# baseControl.net
KiCad netlist of a schematic drawn in Altium Designer
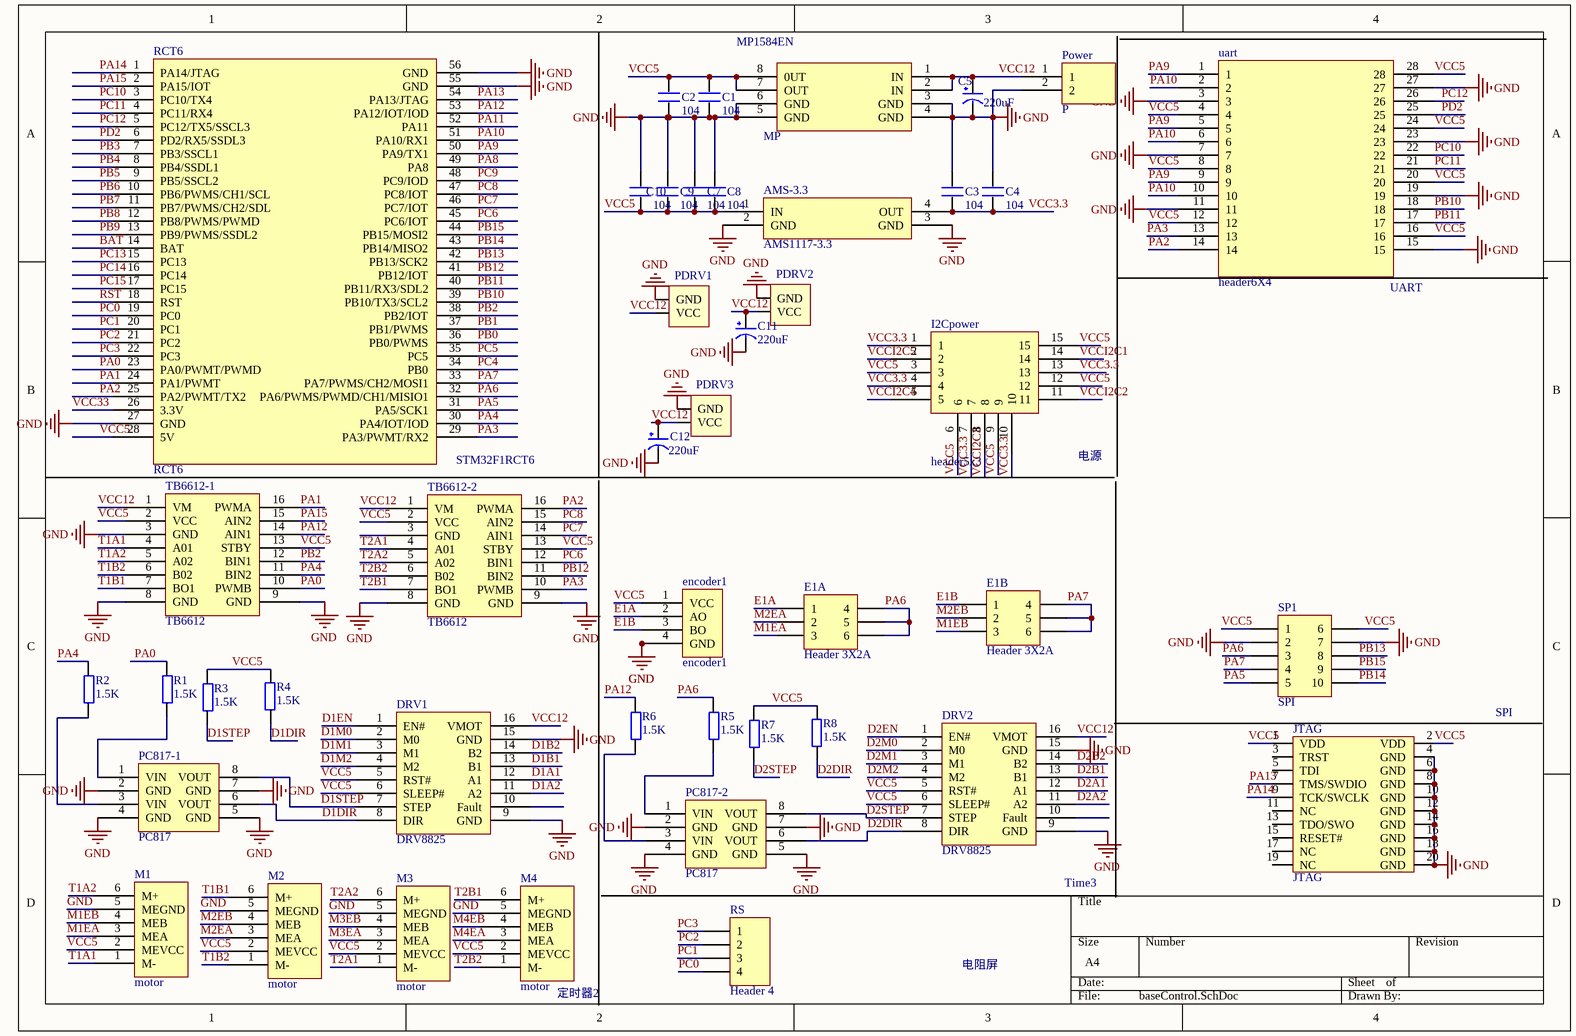
[diagram p0: baseControl.SchDoc]

(export (version "E")
  (design (tool "Eeschema 10.0.6"))
  (components
    (comp (ref "AMS-3.3")
      (value "AMS1117-3.3")
      (footprint "AMS1117-3.3")
      (libsource (lib "controlBsae") (part "AMS1117-3.3"))
    )
    (comp (ref "C1") (value "104") (footprint "0603P") (libsource (lib "CORE") (part "C")))
    (comp (ref "C2") (value "104") (footprint "0603P") (libsource (lib "CORE") (part "C")))
    (comp (ref "C3") (value "104") (footprint "0603P") (libsource (lib "CORE") (part "C")))
    (comp (ref "C4") (value "104") (footprint "0603P") (libsource (lib "CORE") (part "C")))
    (comp (ref "C5") (value "220uF") (footprint "220 25V") (libsource (lib "CORE") (part "CAP")))
    (comp (ref "C7") (value "104") (footprint "0805") (libsource (lib "CORE") (part "C")))
    (comp (ref "C8") (value "104") (footprint "0805") (libsource (lib "CORE") (part "C")))
    (comp (ref "C9") (value "104") (footprint "0805") (libsource (lib "CORE") (part "C")))
    (comp (ref "C10") (value "104") (footprint "0805") (libsource (lib "CORE") (part "C")))
    (comp (ref "C11") (value "220uF") (footprint "220 25V") (libsource (lib "CORE") (part "CAP")))
    (comp (ref "C12") (value "220uF") (footprint "220 25V") (libsource (lib "CORE") (part "CAP")))
    (comp (ref "DRV1")
      (value "DRV8825")
      (footprint "DRV8825")
      (libsource (lib "controlBsae") (part "DRV8825"))
    )
    (comp (ref "DRV2")
      (value "DRV8825")
      (footprint "DRV8825")
      (libsource (lib "controlBsae") (part "DRV8825"))
    )
    (comp (ref "E1A")
      (value "Header 3X2A")
      (footprint "HDR2X3_CEN")
      (description "Header, 3-Pin, Dual row")
      (fields (field (name "PUBLISHER") "Altium Limited"))
      (libsource (lib "Miscellaneous Connectors") (part "Header 3X2A"))
    )
    (comp (ref "E1B")
      (value "Header 3X2A")
      (footprint "HDR2X3_CEN")
      (description "Header, 3-Pin, Dual row")
      (fields (field (name "PUBLISHER") "Altium Limited"))
      (libsource (lib "Miscellaneous Connectors") (part "Header 3X2A"))
    )
    (comp (ref "encoder1")
      (value "encoder1")
      (footprint "XH-4-254")
      (libsource (lib "controlBsae") (part "encoder"))
    )
    (comp (ref "I2Cpower")
      (value "header5x3")
      (footprint "header5X3")
      (libsource (lib "baseControl") (part "header5x3"))
    )
    (comp (ref "JTAG") (value "JTAG") (footprint "JTAG_20") (libsource (lib "CORE") (part "JTAG_20")))
    (comp (ref "M1") (value "motor") (footprint "XH-6-254") (libsource (lib "controlBsae") (part "XH-6-254")))
    (comp (ref "M2") (value "motor") (footprint "XH-6-254") (libsource (lib "controlBsae") (part "XH-6-254")))
    (comp (ref "M3") (value "motor") (footprint "XH-6-254") (libsource (lib "controlBsae") (part "XH-6-254")))
    (comp (ref "M4") (value "motor") (footprint "XH-6-254") (libsource (lib "controlBsae") (part "XH-6-254")))
    (comp (ref "MP")
      (value "MP1584EN")
      (footprint "MP1584EN")
      (libsource (lib "controlBsae") (part "MP1584EN"))
    )
    (comp (ref "PC817-1") (value "PC817") (footprint "DIP4") (libsource (lib "controlBsae") (part "PC817")))
    (comp (ref "PC817-2") (value "PC817") (footprint "DIP4") (libsource (lib "controlBsae") (part "PC817")))
    (comp (ref "PDRV1")
      (value "XH2.54-2P")
      (footprint "XH2.54-2P")
      (libsource (lib "CORE") (part "XH2.54-2P"))
    )
    (comp (ref "PDRV2")
      (value "XH2.54-2P")
      (footprint "XH2.54-2P")
      (libsource (lib "CORE") (part "XH2.54-2P"))
    )
    (comp (ref "PDRV3")
      (value "XH2.54-2P")
      (footprint "XH2.54-2P")
      (libsource (lib "CORE") (part "XH2.54-2P"))
    )
    (comp (ref "Power") (value "P") (footprint "Power") (libsource (lib "controlBsae") (part "Power")))
    (comp (ref "R1") (value "1.5K") (footprint "0603P") (libsource (lib "CORE") (part "R")))
    (comp (ref "R2") (value "1.5K") (footprint "0603P") (libsource (lib "CORE") (part "R")))
    (comp (ref "R3") (value "1.5K") (footprint "0603P") (libsource (lib "CORE") (part "R")))
    (comp (ref "R4") (value "1.5K") (footprint "0603P") (libsource (lib "CORE") (part "R")))
    (comp (ref "R5") (value "1.5K") (footprint "0603P") (libsource (lib "CORE") (part "R")))
    (comp (ref "R6") (value "1.5K") (footprint "0603P") (libsource (lib "CORE") (part "R")))
    (comp (ref "R7") (value "1.5K") (footprint "0603P") (libsource (lib "CORE") (part "R")))
    (comp (ref "R8") (value "1.5K") (footprint "0603P") (libsource (lib "CORE") (part "R")))
    (comp (ref "RCT6")
      (value "RCT6")
      (footprint "STM32F1RCT6")
      (libsource (lib "controlBsae") (part "STM32F1RCT6"))
    )
    (comp (ref "RS")
      (value "Header 4")
      (footprint "HDR1X4")
      (description "Header, 4-Pin")
      (fields (field (name "PUBLISHER") "Altium Limited"))
      (libsource (lib "Miscellaneous Connectors") (part "Header 4"))
    )
    (comp (ref "SP1")
      (value "SPI")
      (footprint "HDR2X5_CEN")
      (description "Header, 5-Pin, Dual row")
      (fields (field (name "PUBLISHER") "Altium Limited"))
      (libsource (lib "Miscellaneous Connectors") (part "Header 5X2A"))
    )
    (comp (ref "TB6612-1")
      (value "TB6612")
      (footprint "TB6612")
      (libsource (lib "controlBsae") (part "TB6612"))
    )
    (comp (ref "TB6612-2")
      (value "TB6612")
      (footprint "TB6612")
      (libsource (lib "controlBsae") (part "TB6612"))
    )
    (comp (ref "uart")
      (value "header6X4")
      (footprint "header7X4")
      (libsource (lib "baseControl") (part "header6X4"))
    )
  )
  (nets
    (net (code "1") (name "/BAT") (class "Default")
      (node (ref "RCT6") (pin "14") (pinfunction "BAT_14") (pintype "passive"))
    )
    (net (code "2") (name "/D1A1") (class "Default")
      (node (ref "DRV1") (pin "12") (pinfunction "A1_12") (pintype "passive"))
    )
    (net (code "3") (name "/D1A2") (class "Default")
      (node (ref "DRV1") (pin "11") (pinfunction "A2_11") (pintype "passive"))
    )
    (net (code "4") (name "/D1B1") (class "Default")
      (node (ref "DRV1") (pin "13") (pinfunction "B1_13") (pintype "passive"))
    )
    (net (code "5") (name "/D1B2") (class "Default")
      (node (ref "DRV1") (pin "14") (pinfunction "B2_14") (pintype "passive"))
    )
    (net (code "6") (name "/D1DIR") (class "Default")
      (node (ref "DRV1") (pin "8") (pinfunction "DIR_8") (pintype "passive"))
      (node (ref "PC817-1") (pin "6") (pinfunction "VOUT_6") (pintype "passive"))
      (node (ref "R4") (pin "2") (pintype "passive"))
    )
    (net (code "7") (name "/D1EN") (class "Default")
      (node (ref "DRV1") (pin "1") (pinfunction "EN#_1") (pintype "passive"))
    )
    (net (code "8") (name "/D1M0") (class "Default")
      (node (ref "DRV1") (pin "2") (pinfunction "M0_2") (pintype "passive"))
    )
    (net (code "9") (name "/D1M1") (class "Default")
      (node (ref "DRV1") (pin "3") (pinfunction "M1_3") (pintype "passive"))
    )
    (net (code "10") (name "/D1M2") (class "Default")
      (node (ref "DRV1") (pin "4") (pinfunction "M2_4") (pintype "passive"))
    )
    (net (code "11") (name "/D1STEP") (class "Default")
      (node (ref "DRV1") (pin "7") (pinfunction "STEP_7") (pintype "passive"))
      (node (ref "PC817-1") (pin "8") (pinfunction "VOUT_8") (pintype "passive"))
      (node (ref "R3") (pin "1") (pintype "passive"))
    )
    (net (code "12") (name "/D2A1") (class "Default")
      (node (ref "DRV2") (pin "12") (pinfunction "A1_12") (pintype "passive"))
    )
    (net (code "13") (name "/D2A2") (class "Default")
      (node (ref "DRV2") (pin "11") (pinfunction "A2_11") (pintype "passive"))
    )
    (net (code "14") (name "/D2B1") (class "Default")
      (node (ref "DRV2") (pin "13") (pinfunction "B1_13") (pintype "passive"))
    )
    (net (code "15") (name "/D2B2") (class "Default")
      (node (ref "DRV2") (pin "14") (pinfunction "B2_14") (pintype "passive"))
    )
    (net (code "16") (name "/D2DIR") (class "Default")
      (node (ref "DRV2") (pin "8") (pinfunction "DIR_8") (pintype "passive"))
      (node (ref "PC817-2") (pin "6") (pinfunction "VOUT_6") (pintype "passive"))
      (node (ref "R8") (pin "2") (pintype "passive"))
    )
    (net (code "17") (name "/D2EN") (class "Default")
      (node (ref "DRV2") (pin "1") (pinfunction "EN#_1") (pintype "passive"))
    )
    (net (code "18") (name "/D2M0") (class "Default")
      (node (ref "DRV2") (pin "2") (pinfunction "M0_2") (pintype "passive"))
    )
    (net (code "19") (name "/D2M1") (class "Default")
      (node (ref "DRV2") (pin "3") (pinfunction "M1_3") (pintype "passive"))
    )
    (net (code "20") (name "/D2M2") (class "Default")
      (node (ref "DRV2") (pin "4") (pinfunction "M2_4") (pintype "passive"))
    )
    (net (code "21") (name "/D2STEP") (class "Default")
      (node (ref "DRV2") (pin "7") (pinfunction "STEP_7") (pintype "passive"))
      (node (ref "PC817-2") (pin "8") (pinfunction "VOUT_8") (pintype "passive"))
      (node (ref "R7") (pin "1") (pintype "passive"))
    )
    (net (code "22") (name "/E1A") (class "Default")
      (node (ref "E1A") (pin "1") (pinfunction "1_1") (pintype "passive"))
      (node (ref "encoder1") (pin "2") (pinfunction "AO_2") (pintype "passive"))
    )
    (net (code "23") (name "/E1B") (class "Default")
      (node (ref "E1B") (pin "1") (pinfunction "1_1") (pintype "passive"))
      (node (ref "encoder1") (pin "3") (pinfunction "BO_3") (pintype "passive"))
    )
    (net (code "24") (name "/M1EA") (class "Default")
      (node (ref "E1A") (pin "3") (pinfunction "3_3") (pintype "passive"))
      (node (ref "M1") (pin "3") (pinfunction "MEA_3") (pintype "passive"))
    )
    (net (code "25") (name "/M1EB") (class "Default")
      (node (ref "E1B") (pin "3") (pinfunction "3_3") (pintype "passive"))
      (node (ref "M1") (pin "4") (pinfunction "MEB_4") (pintype "passive"))
    )
    (net (code "26") (name "/M2EA") (class "Default")
      (node (ref "E1A") (pin "2") (pinfunction "2_2") (pintype "passive"))
      (node (ref "M2") (pin "3") (pinfunction "MEA_3") (pintype "passive"))
    )
    (net (code "27") (name "/M2EB") (class "Default")
      (node (ref "E1B") (pin "2") (pinfunction "2_2") (pintype "passive"))
      (node (ref "M2") (pin "4") (pinfunction "MEB_4") (pintype "passive"))
    )
    (net (code "28") (name "/M3EA") (class "Default")
      (node (ref "M3") (pin "3") (pinfunction "MEA_3") (pintype "passive"))
    )
    (net (code "29") (name "/M3EB") (class "Default")
      (node (ref "M3") (pin "4") (pinfunction "MEB_4") (pintype "passive"))
    )
    (net (code "30") (name "/M4EA") (class "Default")
      (node (ref "M4") (pin "3") (pinfunction "MEA_3") (pintype "passive"))
    )
    (net (code "31") (name "/M4EB") (class "Default")
      (node (ref "M4") (pin "4") (pinfunction "MEB_4") (pintype "passive"))
    )
    (net (code "32") (name "/PA0") (class "Default")
      (node (ref "R1") (pin "2") (pintype "passive"))
      (node (ref "RCT6") (pin "23") (pinfunction "PA0/PWMT/PWMD_23") (pintype "passive"))
      (node (ref "TB6612-1") (pin "10") (pinfunction "PWMB_10") (pintype "passive"))
    )
    (net (code "33") (name "/PA1") (class "Default")
      (node (ref "RCT6") (pin "24") (pinfunction "PA1/PWMT_24") (pintype "passive"))
      (node (ref "TB6612-1") (pin "16") (pinfunction "PWMA_16") (pintype "passive"))
    )
    (net (code "34") (name "/PA2") (class "Default")
      (node (ref "RCT6") (pin "25") (pinfunction "PA2/PWMT/TX2_25") (pintype "passive"))
      (node (ref "TB6612-2") (pin "16") (pinfunction "PWMA_16") (pintype "passive"))
      (node (ref "uart") (pin "14") (pinfunction "14_14") (pintype "passive"))
    )
    (net (code "35") (name "/PA3") (class "Default")
      (node (ref "RCT6") (pin "29") (pinfunction "PA3/PWMT/RX2_29") (pintype "passive"))
      (node (ref "TB6612-2") (pin "10") (pinfunction "PWMB_10") (pintype "passive"))
      (node (ref "uart") (pin "13") (pinfunction "13_13") (pintype "passive"))
    )
    (net (code "36") (name "/PA4") (class "Default")
      (node (ref "R2") (pin "2") (pintype "passive"))
      (node (ref "RCT6") (pin "30") (pinfunction "PA4/IOT/IOD_30") (pintype "passive"))
      (node (ref "TB6612-1") (pin "11") (pinfunction "BIN2_11") (pintype "passive"))
    )
    (net (code "37") (name "/PA5") (class "Default")
      (node (ref "RCT6") (pin "31") (pinfunction "PA5/SCK1_31") (pintype "passive"))
      (node (ref "SP1") (pin "5") (pinfunction "5_5") (pintype "passive"))
    )
    (net (code "38") (name "/PA6") (class "Default")
      (node (ref "E1A") (pin "4") (pinfunction "4_4") (pintype "passive"))
      (node (ref "E1A") (pin "5") (pinfunction "5_5") (pintype "passive"))
      (node (ref "E1A") (pin "6") (pinfunction "6_6") (pintype "passive"))
      (node (ref "R5") (pin "2") (pintype "passive"))
      (node (ref "RCT6") (pin "32") (pinfunction "PA6/PWMS/PWMD/CH1/MISIO1_32") (pintype "passive"))
      (node (ref "SP1") (pin "3") (pinfunction "3_3") (pintype "passive"))
    )
    (net (code "39") (name "/PA7") (class "Default")
      (node (ref "E1B") (pin "4") (pinfunction "4_4") (pintype "passive"))
      (node (ref "E1B") (pin "5") (pinfunction "5_5") (pintype "passive"))
      (node (ref "E1B") (pin "6") (pinfunction "6_6") (pintype "passive"))
      (node (ref "RCT6") (pin "33") (pinfunction "PA7/PWMS/CH2/MOSI1_33") (pintype "passive"))
      (node (ref "SP1") (pin "4") (pinfunction "4_4") (pintype "passive"))
    )
    (net (code "40") (name "/PA8") (class "Default")
      (node (ref "RCT6") (pin "49") (pinfunction "PA8_49") (pintype "passive"))
    )
    (net (code "41") (name "/PA9") (class "Default")
      (node (ref "RCT6") (pin "50") (pinfunction "PA9/TX1_50") (pintype "passive"))
      (node (ref "uart") (pin "1") (pinfunction "1_1") (pintype "passive"))
      (node (ref "uart") (pin "5") (pinfunction "5_5") (pintype "passive"))
      (node (ref "uart") (pin "9") (pinfunction "9_9") (pintype "passive"))
    )
    (net (code "42") (name "/PA10") (class "Default")
      (node (ref "RCT6") (pin "51") (pinfunction "PA10/RX1_51") (pintype "passive"))
      (node (ref "uart") (pin "10") (pinfunction "10_10") (pintype "passive"))
      (node (ref "uart") (pin "2") (pinfunction "2_2") (pintype "passive"))
      (node (ref "uart") (pin "6") (pinfunction "6_6") (pintype "passive"))
    )
    (net (code "43") (name "/PA11") (class "Default")
      (node (ref "RCT6") (pin "52") (pinfunction "PA11_52") (pintype "passive"))
    )
    (net (code "44") (name "/PA12") (class "Default")
      (node (ref "R6") (pin "2") (pintype "passive"))
      (node (ref "RCT6") (pin "53") (pinfunction "PA12/IOT/IOD_53") (pintype "passive"))
      (node (ref "TB6612-1") (pin "14") (pinfunction "AIN1_14") (pintype "passive"))
    )
    (net (code "45") (name "/PA13") (class "Default")
      (node (ref "JTAG") (pin "7") (pinfunction "TMS/SWDIO_7") (pintype "passive"))
      (node (ref "RCT6") (pin "54") (pinfunction "PA13/JTAG_54") (pintype "passive"))
    )
    (net (code "46") (name "/PA14") (class "Default")
      (node (ref "JTAG") (pin "9") (pinfunction "TCK/SWCLK_9") (pintype "passive"))
      (node (ref "RCT6") (pin "1") (pinfunction "PA14/JTAG_1") (pintype "passive"))
    )
    (net (code "47") (name "/PA15") (class "Default")
      (node (ref "RCT6") (pin "2") (pinfunction "PA15/IOT_2") (pintype "passive"))
      (node (ref "TB6612-1") (pin "15") (pinfunction "AIN2_15") (pintype "passive"))
    )
    (net (code "48") (name "/PB0") (class "Default")
      (node (ref "RCT6") (pin "36") (pinfunction "PB0/PWMS_36") (pintype "passive"))
    )
    (net (code "49") (name "/PB1") (class "Default")
      (node (ref "RCT6") (pin "37") (pinfunction "PB1/PWMS_37") (pintype "passive"))
    )
    (net (code "50") (name "/PB2") (class "Default")
      (node (ref "RCT6") (pin "38") (pinfunction "PB2/IOT_38") (pintype "passive"))
      (node (ref "TB6612-1") (pin "12") (pinfunction "BIN1_12") (pintype "passive"))
    )
    (net (code "51") (name "/PB3") (class "Default")
      (node (ref "RCT6") (pin "7") (pinfunction "PB3/SSCL1_7") (pintype "passive"))
    )
    (net (code "52") (name "/PB4") (class "Default")
      (node (ref "RCT6") (pin "8") (pinfunction "PB4/SSDL1_8") (pintype "passive"))
    )
    (net (code "53") (name "/PB5") (class "Default")
      (node (ref "RCT6") (pin "9") (pinfunction "PB5/SSCL2_9") (pintype "passive"))
    )
    (net (code "54") (name "/PB6") (class "Default")
      (node (ref "RCT6") (pin "10") (pinfunction "PB6/PWMS/CH1/SCL_10") (pintype "passive"))
    )
    (net (code "55") (name "/PB7") (class "Default")
      (node (ref "RCT6") (pin "11") (pinfunction "PB7/PWMS/CH2/SDL_11") (pintype "passive"))
    )
    (net (code "56") (name "/PB8") (class "Default")
      (node (ref "RCT6") (pin "12") (pinfunction "PB8/PWMS/PWMD_12") (pintype "passive"))
    )
    (net (code "57") (name "/PB9") (class "Default")
      (node (ref "RCT6") (pin "13") (pinfunction "PB9/PWMS/SSDL2_13") (pintype "passive"))
    )
    (net (code "58") (name "/PB10") (class "Default")
      (node (ref "RCT6") (pin "39") (pinfunction "PB10/TX3/SCL2_39") (pintype "passive"))
      (node (ref "uart") (pin "18") (pinfunction "18_18") (pintype "passive"))
    )
    (net (code "59") (name "/PB11") (class "Default")
      (node (ref "RCT6") (pin "40") (pinfunction "PB11/RX3/SDL2_40") (pintype "passive"))
      (node (ref "uart") (pin "17") (pinfunction "17_17") (pintype "passive"))
    )
    (net (code "60") (name "/PB12") (class "Default")
      (node (ref "RCT6") (pin "41") (pinfunction "PB12/IOT_41") (pintype "passive"))
      (node (ref "TB6612-2") (pin "11") (pinfunction "BIN2_11") (pintype "passive"))
    )
    (net (code "61") (name "/PB13") (class "Default")
      (node (ref "RCT6") (pin "42") (pinfunction "PB13/SCK2_42") (pintype "passive"))
      (node (ref "SP1") (pin "8") (pinfunction "8_8") (pintype "passive"))
    )
    (net (code "62") (name "/PB14") (class "Default")
      (node (ref "RCT6") (pin "43") (pinfunction "PB14/MISO2_43") (pintype "passive"))
      (node (ref "SP1") (pin "10") (pinfunction "10_10") (pintype "passive"))
    )
    (net (code "63") (name "/PB15") (class "Default")
      (node (ref "RCT6") (pin "44") (pinfunction "PB15/MOSI2_44") (pintype "passive"))
      (node (ref "SP1") (pin "9") (pinfunction "9_9") (pintype "passive"))
    )
    (net (code "64") (name "/PC0") (class "Default")
      (node (ref "RCT6") (pin "19") (pinfunction "PC0_19") (pintype "passive"))
      (node (ref "RS") (pin "4") (pinfunction "4_4") (pintype "passive"))
    )
    (net (code "65") (name "/PC1") (class "Default")
      (node (ref "RCT6") (pin "20") (pinfunction "PC1_20") (pintype "passive"))
      (node (ref "RS") (pin "3") (pinfunction "3_3") (pintype "passive"))
    )
    (net (code "66") (name "/PC2") (class "Default")
      (node (ref "RCT6") (pin "21") (pinfunction "PC2_21") (pintype "passive"))
      (node (ref "RS") (pin "2") (pinfunction "2_2") (pintype "passive"))
    )
    (net (code "67") (name "/PC3") (class "Default")
      (node (ref "RCT6") (pin "22") (pinfunction "PC3_22") (pintype "passive"))
      (node (ref "RS") (pin "1") (pinfunction "1_1") (pintype "passive"))
    )
    (net (code "68") (name "/PC4") (class "Default")
      (node (ref "RCT6") (pin "34") (pinfunction "PB0_34") (pintype "passive"))
    )
    (net (code "69") (name "/PC5") (class "Default")
      (node (ref "RCT6") (pin "35") (pinfunction "PC5_35") (pintype "passive"))
    )
    (net (code "70") (name "/PC6") (class "Default")
      (node (ref "RCT6") (pin "45") (pinfunction "PC6/IOT_45") (pintype "passive"))
      (node (ref "TB6612-2") (pin "12") (pinfunction "BIN1_12") (pintype "passive"))
    )
    (net (code "71") (name "/PC7") (class "Default")
      (node (ref "RCT6") (pin "46") (pinfunction "PC7/IOT_46") (pintype "passive"))
      (node (ref "TB6612-2") (pin "14") (pinfunction "AIN1_14") (pintype "passive"))
    )
    (net (code "72") (name "/PC8") (class "Default")
      (node (ref "RCT6") (pin "47") (pinfunction "PC8/IOT_47") (pintype "passive"))
      (node (ref "TB6612-2") (pin "15") (pinfunction "AIN2_15") (pintype "passive"))
    )
    (net (code "73") (name "/PC9") (class "Default")
      (node (ref "RCT6") (pin "48") (pinfunction "PC9/IOD_48") (pintype "passive"))
    )
    (net (code "74") (name "/PC10") (class "Default")
      (node (ref "RCT6") (pin "3") (pinfunction "PC10/TX4_3") (pintype "passive"))
      (node (ref "uart") (pin "22") (pinfunction "22_22") (pintype "passive"))
    )
    (net (code "75") (name "/PC11") (class "Default")
      (node (ref "RCT6") (pin "4") (pinfunction "PC11/RX4_4") (pintype "passive"))
      (node (ref "uart") (pin "21") (pinfunction "21_21") (pintype "passive"))
    )
    (net (code "76") (name "/PC12") (class "Default")
      (node (ref "RCT6") (pin "5") (pinfunction "PC12/TX5/SSCL3_5") (pintype "passive"))
      (node (ref "uart") (pin "26") (pinfunction "26_26") (pintype "passive"))
    )
    (net (code "77") (name "/PC13") (class "Default")
      (node (ref "RCT6") (pin "15") (pinfunction "PC13_15") (pintype "passive"))
    )
    (net (code "78") (name "/PC14") (class "Default")
      (node (ref "RCT6") (pin "16") (pinfunction "PC14_16") (pintype "passive"))
    )
    (net (code "79") (name "/PC15") (class "Default")
      (node (ref "RCT6") (pin "17") (pinfunction "PC15_17") (pintype "passive"))
    )
    (net (code "80") (name "/PD2") (class "Default")
      (node (ref "RCT6") (pin "6") (pinfunction "PD2/RX5/SSDL3_6") (pintype "passive"))
      (node (ref "uart") (pin "25") (pinfunction "25_25") (pintype "passive"))
    )
    (net (code "81") (name "/RST") (class "Default")
      (node (ref "RCT6") (pin "18") (pinfunction "RST_18") (pintype "passive"))
    )
    (net (code "82") (name "/T1A1") (class "Default")
      (node (ref "M1") (pin "1") (pinfunction "M-_1") (pintype "passive"))
      (node (ref "TB6612-1") (pin "4") (pinfunction "A01_4") (pintype "passive"))
    )
    (net (code "83") (name "/T1A2") (class "Default")
      (node (ref "M1") (pin "6") (pinfunction "M+_6") (pintype "passive"))
      (node (ref "TB6612-1") (pin "5") (pinfunction "A02_5") (pintype "passive"))
    )
    (net (code "84") (name "/T1B1") (class "Default")
      (node (ref "M2") (pin "6") (pinfunction "M+_6") (pintype "passive"))
      (node (ref "TB6612-1") (pin "7") (pinfunction "BO1_7") (pintype "passive"))
    )
    (net (code "85") (name "/T1B2") (class "Default")
      (node (ref "M2") (pin "1") (pinfunction "M-_1") (pintype "passive"))
      (node (ref "TB6612-1") (pin "6") (pinfunction "B02_6") (pintype "passive"))
    )
    (net (code "86") (name "/T2A1") (class "Default")
      (node (ref "M3") (pin "1") (pinfunction "M-_1") (pintype "passive"))
      (node (ref "TB6612-2") (pin "4") (pinfunction "A01_4") (pintype "passive"))
    )
    (net (code "87") (name "/T2A2") (class "Default")
      (node (ref "M3") (pin "6") (pinfunction "M+_6") (pintype "passive"))
      (node (ref "TB6612-2") (pin "5") (pinfunction "A02_5") (pintype "passive"))
    )
    (net (code "88") (name "/T2B1") (class "Default")
      (node (ref "M4") (pin "6") (pinfunction "M+_6") (pintype "passive"))
      (node (ref "TB6612-2") (pin "7") (pinfunction "BO1_7") (pintype "passive"))
    )
    (net (code "89") (name "/T2B2") (class "Default")
      (node (ref "M4") (pin "1") (pinfunction "M-_1") (pintype "passive"))
      (node (ref "TB6612-2") (pin "6") (pinfunction "B02_6") (pintype "passive"))
    )
    (net (code "90") (name "/VCC3.3") (class "Default")
      (node (ref "AMS-3.3") (pin "4") (pinfunction "OUT_4") (pintype "passive"))
      (node (ref "C3") (pin "1") (pintype "passive"))
      (node (ref "C4") (pin "1") (pintype "passive"))
      (node (ref "I2Cpower") (pin "1") (pinfunction "1_1") (pintype "passive"))
      (node (ref "I2Cpower") (pin "10") (pinfunction "10_10") (pintype "passive"))
      (node (ref "I2Cpower") (pin "13") (pinfunction "13_13") (pintype "passive"))
      (node (ref "I2Cpower") (pin "4") (pinfunction "4_4") (pintype "passive"))
      (node (ref "I2Cpower") (pin "7") (pinfunction "7_7") (pintype "passive"))
    )
    (net (code "91") (name "/VCC5") (class "Default")
      (node (ref "AMS-3.3") (pin "1") (pinfunction "IN_1") (pintype "passive"))
      (node (ref "C1") (pin "1") (pintype "passive"))
      (node (ref "C10") (pin "1") (pintype "passive"))
      (node (ref "C2") (pin "1") (pintype "passive"))
      (node (ref "C7") (pin "1") (pintype "passive"))
      (node (ref "C8") (pin "1") (pintype "passive"))
      (node (ref "C9") (pin "1") (pintype "passive"))
      (node (ref "DRV1") (pin "5") (pinfunction "RST#_5") (pintype "passive"))
      (node (ref "DRV1") (pin "6") (pinfunction "SLEEP#_6") (pintype "passive"))
      (node (ref "DRV2") (pin "5") (pinfunction "RST#_5") (pintype "passive"))
      (node (ref "DRV2") (pin "6") (pinfunction "SLEEP#_6") (pintype "passive"))
      (node (ref "I2Cpower") (pin "12") (pinfunction "12_12") (pintype "passive"))
      (node (ref "I2Cpower") (pin "15") (pinfunction "15_15") (pintype "passive"))
      (node (ref "I2Cpower") (pin "3") (pinfunction "3_3") (pintype "passive"))
      (node (ref "I2Cpower") (pin "6") (pinfunction "6_6") (pintype "passive"))
      (node (ref "I2Cpower") (pin "9") (pinfunction "9_9") (pintype "passive"))
      (node (ref "JTAG") (pin "1") (pinfunction "VDD_1") (pintype "passive"))
      (node (ref "JTAG") (pin "2") (pinfunction "VDD_2") (pintype "passive"))
      (node (ref "M1") (pin "2") (pinfunction "MEVCC_2") (pintype "passive"))
      (node (ref "M2") (pin "2") (pinfunction "MEVCC_2") (pintype "passive"))
      (node (ref "M3") (pin "2") (pinfunction "MEVCC_2") (pintype "passive"))
      (node (ref "M4") (pin "2") (pinfunction "MEVCC_2") (pintype "passive"))
      (node (ref "MP") (pin "7") (pinfunction "OUT_7") (pintype "passive"))
      (node (ref "MP") (pin "8") (pinfunction "0UT_8") (pintype "passive"))
      (node (ref "R3") (pin "2") (pintype "passive"))
      (node (ref "R4") (pin "1") (pintype "passive"))
      (node (ref "R7") (pin "2") (pintype "passive"))
      (node (ref "R8") (pin "1") (pintype "passive"))
      (node (ref "RCT6") (pin "28") (pinfunction "5V_28") (pintype "passive"))
      (node (ref "SP1") (pin "1") (pinfunction "1_1") (pintype "passive"))
      (node (ref "SP1") (pin "6") (pinfunction "6_6") (pintype "passive"))
      (node (ref "TB6612-1") (pin "13") (pinfunction "STBY_13") (pintype "passive"))
      (node (ref "TB6612-1") (pin "2") (pinfunction "VCC_2") (pintype "passive"))
      (node (ref "TB6612-2") (pin "13") (pinfunction "STBY_13") (pintype "passive"))
      (node (ref "TB6612-2") (pin "2") (pinfunction "VCC_2") (pintype "passive"))
      (node (ref "encoder1") (pin "1") (pinfunction "VCC_1") (pintype "passive"))
      (node (ref "uart") (pin "12") (pinfunction "12_12") (pintype "passive"))
      (node (ref "uart") (pin "16") (pinfunction "16_16") (pintype "passive"))
      (node (ref "uart") (pin "20") (pinfunction "20_20") (pintype "passive"))
      (node (ref "uart") (pin "24") (pinfunction "24_24") (pintype "passive"))
      (node (ref "uart") (pin "28") (pinfunction "28_28") (pintype "passive"))
      (node (ref "uart") (pin "4") (pinfunction "4_4") (pintype "passive"))
      (node (ref "uart") (pin "8") (pinfunction "8_8") (pintype "passive"))
    )
    (net (code "92") (name "/VCC12") (class "Default")
      (node (ref "C11") (pin "1") (pinfunction "VCC_1") (pintype "passive"))
      (node (ref "C12") (pin "1") (pinfunction "VCC_1") (pintype "passive"))
      (node (ref "C5") (pin "1") (pinfunction "VCC_1") (pintype "passive"))
      (node (ref "DRV1") (pin "16") (pinfunction "VMOT_16") (pintype "passive"))
      (node (ref "DRV2") (pin "16") (pinfunction "VMOT_16") (pintype "passive"))
      (node (ref "MP") (pin "1") (pinfunction "IN_1") (pintype "passive"))
      (node (ref "MP") (pin "2") (pinfunction "IN_2") (pintype "passive"))
      (node (ref "PDRV1") (pin "2") (pinfunction "VCC_2") (pintype "passive"))
      (node (ref "PDRV2") (pin "2") (pinfunction "VCC_2") (pintype "passive"))
      (node (ref "PDRV3") (pin "2") (pinfunction "VCC_2") (pintype "passive"))
      (node (ref "Power") (pin "1") (pinfunction "1_1") (pintype "passive"))
      (node (ref "TB6612-1") (pin "1") (pinfunction "VM_1") (pintype "passive"))
      (node (ref "TB6612-2") (pin "1") (pinfunction "VM_1") (pintype "passive"))
    )
    (net (code "93") (name "/VCC33") (class "Default")
      (node (ref "RCT6") (pin "26") (pinfunction "3.3V_26") (pintype "passive"))
    )
    (net (code "94") (name "/VCCI2C1") (class "Default")
      (node (ref "I2Cpower") (pin "14") (pinfunction "14_14") (pintype "passive"))
    )
    (net (code "95") (name "/VCCI2C2") (class "Default")
      (node (ref "I2Cpower") (pin "11") (pinfunction "11_11") (pintype "passive"))
    )
    (net (code "96") (name "/VCCI2C3") (class "Default")
      (node (ref "I2Cpower") (pin "8") (pinfunction "8_8") (pintype "passive"))
    )
    (net (code "97") (name "/VCCI2C4") (class "Default")
      (node (ref "I2Cpower") (pin "5") (pinfunction "5_5") (pintype "passive"))
    )
    (net (code "98") (name "/VCCI2C5") (class "Default")
      (node (ref "I2Cpower") (pin "2") (pinfunction "2_2") (pintype "passive"))
    )
    (net (code "99") (name "GND") (class "Default")
      (node (ref "AMS-3.3") (pin "2") (pinfunction "GND_2") (pintype "passive"))
      (node (ref "AMS-3.3") (pin "3") (pinfunction "GND_3") (pintype "passive"))
      (node (ref "C1") (pin "2") (pintype "passive"))
      (node (ref "C10") (pin "2") (pintype "passive"))
      (node (ref "C11") (pin "2") (pinfunction "GND_2") (pintype "passive"))
      (node (ref "C12") (pin "2") (pinfunction "GND_2") (pintype "passive"))
      (node (ref "C2") (pin "2") (pintype "passive"))
      (node (ref "C3") (pin "2") (pintype "passive"))
      (node (ref "C4") (pin "2") (pintype "passive"))
      (node (ref "C5") (pin "2") (pinfunction "GND_2") (pintype "passive"))
      (node (ref "C7") (pin "2") (pintype "passive"))
      (node (ref "C8") (pin "2") (pintype "passive"))
      (node (ref "C9") (pin "2") (pintype "passive"))
      (node (ref "DRV1") (pin "15") (pinfunction "GND_15") (pintype "passive"))
      (node (ref "DRV1") (pin "9") (pinfunction "GND_9") (pintype "passive"))
      (node (ref "DRV2") (pin "15") (pinfunction "GND_15") (pintype "passive"))
      (node (ref "DRV2") (pin "9") (pinfunction "GND_9") (pintype "passive"))
      (node (ref "JTAG") (pin "10") (pinfunction "GND_10") (pintype "passive"))
      (node (ref "JTAG") (pin "12") (pinfunction "GND_12") (pintype "passive"))
      (node (ref "JTAG") (pin "14") (pinfunction "GND_14") (pintype "passive"))
      (node (ref "JTAG") (pin "16") (pinfunction "GND_16") (pintype "passive"))
      (node (ref "JTAG") (pin "18") (pinfunction "GND_18") (pintype "passive"))
      (node (ref "JTAG") (pin "20") (pinfunction "GND_20") (pintype "passive"))
      (node (ref "JTAG") (pin "4") (pinfunction "GND_4") (pintype "passive"))
      (node (ref "JTAG") (pin "6") (pinfunction "GND_6") (pintype "passive"))
      (node (ref "JTAG") (pin "8") (pinfunction "GND_8") (pintype "passive"))
      (node (ref "M1") (pin "5") (pinfunction "MEGND_5") (pintype "passive"))
      (node (ref "M2") (pin "5") (pinfunction "MEGND_5") (pintype "passive"))
      (node (ref "M3") (pin "5") (pinfunction "MEGND_5") (pintype "passive"))
      (node (ref "M4") (pin "5") (pinfunction "MEGND_5") (pintype "passive"))
      (node (ref "MP") (pin "3") (pinfunction "GND_3") (pintype "passive"))
      (node (ref "MP") (pin "4") (pinfunction "GND_4") (pintype "passive"))
      (node (ref "MP") (pin "5") (pinfunction "GND_5") (pintype "passive"))
      (node (ref "MP") (pin "6") (pinfunction "GND_6") (pintype "passive"))
      (node (ref "PC817-1") (pin "2") (pinfunction "GND_2") (pintype "passive"))
      (node (ref "PC817-1") (pin "4") (pinfunction "GND_4") (pintype "passive"))
      (node (ref "PC817-1") (pin "5") (pinfunction "GND_5") (pintype "passive"))
      (node (ref "PC817-1") (pin "7") (pinfunction "GND_7") (pintype "passive"))
      (node (ref "PC817-2") (pin "2") (pinfunction "GND_2") (pintype "passive"))
      (node (ref "PC817-2") (pin "4") (pinfunction "GND_4") (pintype "passive"))
      (node (ref "PC817-2") (pin "5") (pinfunction "GND_5") (pintype "passive"))
      (node (ref "PC817-2") (pin "7") (pinfunction "GND_7") (pintype "passive"))
      (node (ref "PDRV1") (pin "1") (pinfunction "GND_1") (pintype "passive"))
      (node (ref "PDRV2") (pin "1") (pinfunction "GND_1") (pintype "passive"))
      (node (ref "PDRV3") (pin "1") (pinfunction "GND_1") (pintype "passive"))
      (node (ref "Power") (pin "2") (pinfunction "2_2") (pintype "passive"))
      (node (ref "RCT6") (pin "27") (pinfunction "GND_27") (pintype "passive"))
      (node (ref "RCT6") (pin "55") (pinfunction "GND_55") (pintype "passive"))
      (node (ref "RCT6") (pin "56") (pinfunction "GND_56") (pintype "passive"))
      (node (ref "SP1") (pin "2") (pinfunction "2_2") (pintype "passive"))
      (node (ref "SP1") (pin "7") (pinfunction "7_7") (pintype "passive"))
      (node (ref "TB6612-1") (pin "3") (pinfunction "GND_3") (pintype "passive"))
      (node (ref "TB6612-1") (pin "8") (pinfunction "GND_8") (pintype "passive"))
      (node (ref "TB6612-1") (pin "9") (pinfunction "GND_9") (pintype "passive"))
      (node (ref "TB6612-2") (pin "8") (pinfunction "GND_8") (pintype "passive"))
      (node (ref "TB6612-2") (pin "9") (pinfunction "GND_9") (pintype "passive"))
      (node (ref "encoder1") (pin "4") (pinfunction "GND_4") (pintype "passive"))
      (node (ref "uart") (pin "11") (pinfunction "11_11") (pintype "passive"))
      (node (ref "uart") (pin "15") (pinfunction "15_15") (pintype "passive"))
      (node (ref "uart") (pin "19") (pinfunction "19_19") (pintype "passive"))
      (node (ref "uart") (pin "23") (pinfunction "23_23") (pintype "passive"))
      (node (ref "uart") (pin "27") (pinfunction "27_27") (pintype "passive"))
      (node (ref "uart") (pin "3") (pinfunction "3_3") (pintype "passive"))
      (node (ref "uart") (pin "7") (pinfunction "7_7") (pintype "passive"))
    )
    (net (code "100") (name "Net-(PC817-1-VIN-Pad1)") (class "Default")
      (node (ref "PC817-1") (pin "1") (pinfunction "VIN_1") (pintype "passive"))
      (node (ref "R1") (pin "1") (pintype "passive"))
    )
    (net (code "101") (name "Net-(PC817-1-VIN-Pad3)") (class "Default")
      (node (ref "PC817-1") (pin "3") (pinfunction "VIN_3") (pintype "passive"))
      (node (ref "R2") (pin "1") (pintype "passive"))
    )
    (net (code "102") (name "Net-(PC817-2-VIN-Pad1)") (class "Default")
      (node (ref "PC817-2") (pin "1") (pinfunction "VIN_1") (pintype "passive"))
      (node (ref "R5") (pin "1") (pintype "passive"))
    )
    (net (code "103") (name "Net-(PC817-2-VIN-Pad3)") (class "Default")
      (node (ref "PC817-2") (pin "3") (pinfunction "VIN_3") (pintype "passive"))
      (node (ref "R6") (pin "1") (pintype "passive"))
    )
    (net (code "104") (name "unconnected-(DRV1-Fault-Pad10)") (class "Default")
      (node (ref "DRV1") (pin "10") (pinfunction "Fault_10") (pintype "passive"))
    )
    (net (code "105") (name "unconnected-(DRV2-Fault-Pad10)") (class "Default")
      (node (ref "DRV2") (pin "10") (pinfunction "Fault_10") (pintype "passive"))
    )
    (net (code "106") (name "unconnected-(JTAG-NC-Pad11)") (class "Default")
      (node (ref "JTAG") (pin "11") (pinfunction "NC_11") (pintype "passive"))
    )
    (net (code "107") (name "unconnected-(JTAG-NC-Pad17)") (class "Default")
      (node (ref "JTAG") (pin "17") (pinfunction "NC_17") (pintype "passive"))
    )
    (net (code "108") (name "unconnected-(JTAG-NC-Pad19)") (class "Default")
      (node (ref "JTAG") (pin "19") (pinfunction "NC_19") (pintype "passive"))
    )
    (net (code "109") (name "unconnected-(JTAG-RESET#-Pad15)") (class "Default")
      (node (ref "JTAG") (pin "15") (pinfunction "RESET#_15") (pintype "passive"))
    )
    (net (code "110") (name "unconnected-(JTAG-TDI-Pad5)") (class "Default")
      (node (ref "JTAG") (pin "5") (pinfunction "TDI_5") (pintype "passive"))
    )
    (net (code "111") (name "unconnected-(JTAG-TDO{slash}SWO-Pad13)") (class "Default")
      (node (ref "JTAG") (pin "13") (pinfunction "TDO/SWO_13") (pintype "passive"))
    )
    (net (code "112") (name "unconnected-(JTAG-TRST-Pad3)") (class "Default")
      (node (ref "JTAG") (pin "3") (pinfunction "TRST_3") (pintype "passive"))
    )
    (net (code "113") (name "unconnected-(TB6612-2-GND-Pad3)") (class "Default")
      (node (ref "TB6612-2") (pin "3") (pinfunction "GND_3") (pintype "passive"))
    )
  )
)
